# Mother_board_SSL2018.net
KiCad netlist of a schematic drawn in Altium Designer
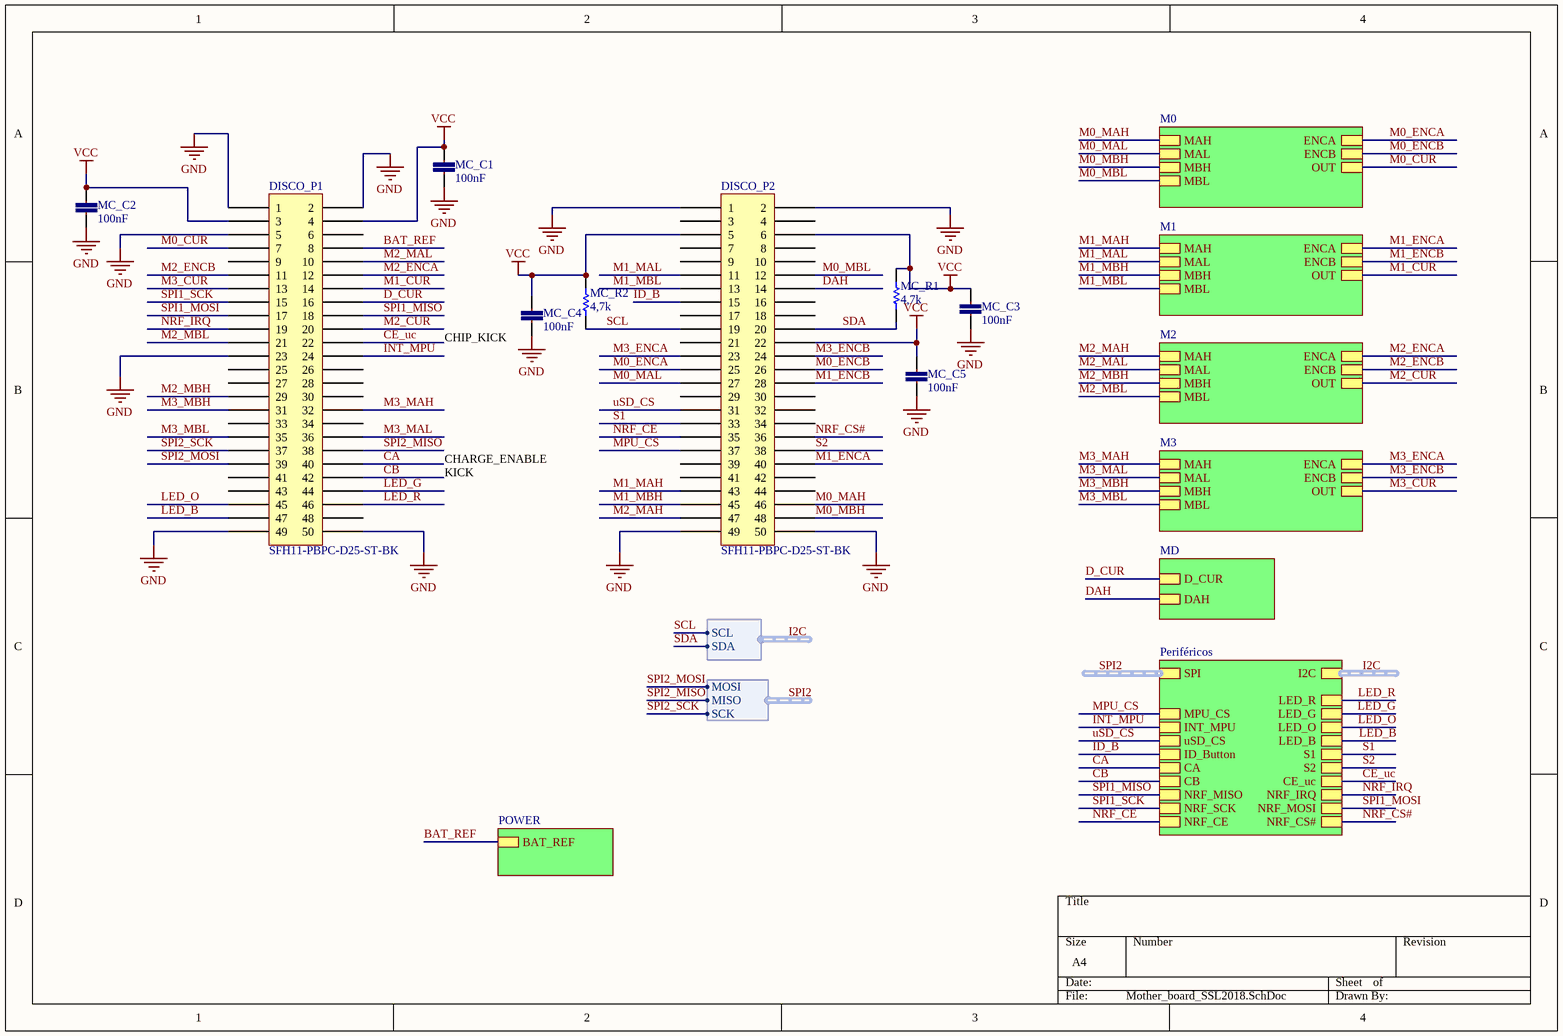
[diagram p0: Mother_board_SSL2018.SchDoc]

(export (version "E")
  (design (tool "Eeschema 10.0.6"))
  (components
    (comp (ref "DISCO_P1")
      (value "SFH11-PBPC-D25-ST-BK")
      (footprint "25x02_Conector_Female")
      (description "50 Position Header Connector 0.100\" (2.54mm) Through Hole Gold")
      (libsource (lib "Schlib1") (part "25x02_Conector_Female"))
    )
    (comp (ref "DISCO_P2")
      (value "SFH11-PBPC-D25-ST-BK")
      (footprint "25x02_Conector_Female")
      (description "50 Position Header Connector 0.100\" (2.54mm) Through Hole Gold")
      (libsource (lib "Schlib1") (part "25x02_Conector_Female"))
    )
    (comp (ref "MC_C1")
      (value "100nF")
      (footprint "0402-CAP")
      (description "CAP CER 0.1UF 10V 20% X5R 0402")
      (fields (field (name "PART NO") "VJ0402V104ZXQPBC"))
      (libsource (lib "") (part "CC0402-100nF-A.12_1"))
    )
    (comp (ref "MC_C2")
      (value "100nF")
      (footprint "0402-CAP")
      (description "CAP CER 0.1UF 10V 20% X5R 0402")
      (fields (field (name "PART NO") "VJ0402V104ZXQPBC"))
      (libsource (lib "IMBEL") (part "CC0402-100nF-A.12"))
    )
    (comp (ref "MC_C3")
      (value "100nF")
      (footprint "0402-CAP")
      (description "CAP CER 0.1UF 10V 20% X5R 0402")
      (fields (field (name "PART NO") "VJ0402V104ZXQPBC"))
      (libsource (lib "") (part "CC0402-100nF-A.12_1"))
    )
    (comp (ref "MC_C4")
      (value "100nF")
      (footprint "0402-CAP")
      (description "CAP CER 0.1UF 10V 20% X5R 0402")
      (fields (field (name "PART NO") "VJ0402V104ZXQPBC"))
      (libsource (lib "") (part "CC0402-100nF-A.12_1"))
    )
    (comp (ref "MC_C5")
      (value "100nF")
      (footprint "0402-CAP")
      (description "CAP CER 0.1UF 10V 20% X5R 0402")
      (fields (field (name "PART NO") "VJ0402V104ZXQPBC"))
      (libsource (lib "") (part "CC0402-100nF-A.12_1"))
    )
    (comp (ref "MC_R1")
      (value "4,7k")
      (footprint "0402")
      (description "Resistor")
      (fields (field (name "PUBLISHER") "Altium Limited"))
      (libsource (lib "Miscellaneous Devices") (part "Res1"))
    )
    (comp (ref "MC_R2")
      (value "4,7k")
      (footprint "0402")
      (description "Resistor")
      (fields (field (name "PUBLISHER") "Altium Limited"))
      (libsource (lib "Miscellaneous Devices") (part "Res1"))
    )
  )
  (nets
    (net (code "5") (name "/BAT_REF") (class "Default")
      (node (ref "DISCO_P1") (pin "8") (pinfunction "8_8") (pintype "passive"))
    )
    (net (code "6") (name "/CA") (class "Default")
      (node (ref "DISCO_P1") (pin "40") (pinfunction "40_40") (pintype "passive"))
    )
    (net (code "7") (name "/CB") (class "Default")
      (node (ref "DISCO_P1") (pin "42") (pinfunction "42_42") (pintype "passive"))
    )
    (net (code "8") (name "/CE_uc") (class "Default")
      (node (ref "DISCO_P1") (pin "22") (pinfunction "22_22") (pintype "passive"))
    )
    (net (code "9") (name "/DAH") (class "Default")
      (node (ref "DISCO_P2") (pin "14") (pinfunction "14_14") (pintype "passive"))
    )
    (net (code "10") (name "/D_CUR") (class "Default")
      (node (ref "DISCO_P1") (pin "16") (pinfunction "16_16") (pintype "passive"))
    )
    (net (code "12") (name "/ID_B") (class "Default")
      (node (ref "DISCO_P2") (pin "15") (pinfunction "15_15") (pintype "passive"))
    )
    (net (code "13") (name "/INT_MPU") (class "Default")
      (node (ref "DISCO_P1") (pin "24") (pinfunction "24_24") (pintype "passive"))
    )
    (net (code "14") (name "/LED_B") (class "Default")
      (node (ref "DISCO_P1") (pin "47") (pinfunction "47_47") (pintype "passive"))
    )
    (net (code "15") (name "/LED_G") (class "Default")
      (node (ref "DISCO_P1") (pin "44") (pinfunction "44_44") (pintype "passive"))
    )
    (net (code "16") (name "/LED_O") (class "Default")
      (node (ref "DISCO_P1") (pin "45") (pinfunction "45_45") (pintype "passive"))
    )
    (net (code "17") (name "/LED_R") (class "Default")
      (node (ref "DISCO_P1") (pin "46") (pinfunction "46_46") (pintype "passive"))
    )
    (net (code "18") (name "/M0_CUR") (class "Default")
      (node (ref "DISCO_P1") (pin "7") (pinfunction "7_7") (pintype "passive"))
    )
    (net (code "19") (name "/M0_ENCA") (class "Default")
      (node (ref "DISCO_P2") (pin "25") (pinfunction "25_25") (pintype "passive"))
    )
    (net (code "20") (name "/M0_ENCB") (class "Default")
      (node (ref "DISCO_P2") (pin "26") (pinfunction "26_26") (pintype "passive"))
    )
    (net (code "21") (name "/M0_MAH") (class "Default")
      (node (ref "DISCO_P2") (pin "46") (pinfunction "46_46") (pintype "passive"))
    )
    (net (code "22") (name "/M0_MAL") (class "Default")
      (node (ref "DISCO_P2") (pin "27") (pinfunction "27_27") (pintype "passive"))
    )
    (net (code "23") (name "/M0_MBH") (class "Default")
      (node (ref "DISCO_P2") (pin "48") (pinfunction "48_48") (pintype "passive"))
    )
    (net (code "24") (name "/M0_MBL") (class "Default")
      (node (ref "DISCO_P2") (pin "12") (pinfunction "12_12") (pintype "passive"))
    )
    (net (code "25") (name "/M1_CUR") (class "Default")
      (node (ref "DISCO_P1") (pin "14") (pinfunction "14_14") (pintype "passive"))
    )
    (net (code "26") (name "/M1_ENCA") (class "Default")
      (node (ref "DISCO_P2") (pin "40") (pinfunction "40_40") (pintype "passive"))
    )
    (net (code "27") (name "/M1_ENCB") (class "Default")
      (node (ref "DISCO_P2") (pin "28") (pinfunction "28_28") (pintype "passive"))
    )
    (net (code "28") (name "/M1_MAH") (class "Default")
      (node (ref "DISCO_P2") (pin "43") (pinfunction "43_43") (pintype "passive"))
    )
    (net (code "29") (name "/M1_MAL") (class "Default")
      (node (ref "DISCO_P2") (pin "11") (pinfunction "11_11") (pintype "passive"))
    )
    (net (code "30") (name "/M1_MBH") (class "Default")
      (node (ref "DISCO_P2") (pin "45") (pinfunction "45_45") (pintype "passive"))
    )
    (net (code "31") (name "/M1_MBL") (class "Default")
      (node (ref "DISCO_P2") (pin "13") (pinfunction "13_13") (pintype "passive"))
    )
    (net (code "32") (name "/M2_CUR") (class "Default")
      (node (ref "DISCO_P1") (pin "20") (pinfunction "20_20") (pintype "passive"))
    )
    (net (code "33") (name "/M2_ENCA") (class "Default")
      (node (ref "DISCO_P1") (pin "12") (pinfunction "12_12") (pintype "passive"))
    )
    (net (code "34") (name "/M2_ENCB") (class "Default")
      (node (ref "DISCO_P1") (pin "11") (pinfunction "11_11") (pintype "passive"))
    )
    (net (code "35") (name "/M2_MAH") (class "Default")
      (node (ref "DISCO_P2") (pin "47") (pinfunction "47_47") (pintype "passive"))
    )
    (net (code "36") (name "/M2_MAL") (class "Default")
      (node (ref "DISCO_P1") (pin "10") (pinfunction "10_10") (pintype "passive"))
    )
    (net (code "37") (name "/M2_MBH") (class "Default")
      (node (ref "DISCO_P1") (pin "29") (pinfunction "29_29") (pintype "passive"))
    )
    (net (code "38") (name "/M2_MBL") (class "Default")
      (node (ref "DISCO_P1") (pin "21") (pinfunction "21_21") (pintype "passive"))
    )
    (net (code "39") (name "/M3_CUR") (class "Default")
      (node (ref "DISCO_P1") (pin "13") (pinfunction "13_13") (pintype "passive"))
    )
    (net (code "40") (name "/M3_ENCA") (class "Default")
      (node (ref "DISCO_P2") (pin "23") (pinfunction "23_23") (pintype "passive"))
    )
    (net (code "41") (name "/M3_ENCB") (class "Default")
      (node (ref "DISCO_P2") (pin "24") (pinfunction "24_24") (pintype "passive"))
    )
    (net (code "42") (name "/M3_MAH") (class "Default")
      (node (ref "DISCO_P1") (pin "32") (pinfunction "32_32") (pintype "passive"))
    )
    (net (code "43") (name "/M3_MAL") (class "Default")
      (node (ref "DISCO_P1") (pin "36") (pinfunction "36_36") (pintype "passive"))
    )
    (net (code "44") (name "/M3_MBH") (class "Default")
      (node (ref "DISCO_P1") (pin "31") (pinfunction "31_31") (pintype "passive"))
    )
    (net (code "45") (name "/M3_MBL") (class "Default")
      (node (ref "DISCO_P1") (pin "35") (pinfunction "35_35") (pintype "passive"))
    )
    (net (code "46") (name "/MPU_CS") (class "Default")
      (node (ref "DISCO_P2") (pin "37") (pinfunction "37_37") (pintype "passive"))
    )
    (net (code "47") (name "/NRF_CE") (class "Default")
      (node (ref "DISCO_P2") (pin "35") (pinfunction "35_35") (pintype "passive"))
    )
    (net (code "48") (name "/NRF_CS#") (class "Default")
      (node (ref "DISCO_P2") (pin "36") (pinfunction "36_36") (pintype "passive"))
    )
    (net (code "49") (name "/NRF_IRQ") (class "Default")
      (node (ref "DISCO_P1") (pin "19") (pinfunction "19_19") (pintype "passive"))
    )
    (net (code "50") (name "/S1") (class "Default")
      (node (ref "DISCO_P2") (pin "33") (pinfunction "33_33") (pintype "passive"))
    )
    (net (code "51") (name "/S2") (class "Default")
      (node (ref "DISCO_P2") (pin "38") (pinfunction "38_38") (pintype "passive"))
    )
    (net (code "52") (name "/SCL") (class "Default")
      (node (ref "DISCO_P2") (pin "19") (pinfunction "19_19") (pintype "passive"))
      (node (ref "MC_R2") (pin "1") (pinfunction "1_1") (pintype "passive"))
    )
    (net (code "53") (name "/SDA") (class "Default")
      (node (ref "DISCO_P2") (pin "20") (pinfunction "20_20") (pintype "passive"))
      (node (ref "MC_R1") (pin "1") (pinfunction "1_1") (pintype "passive"))
    )
    (net (code "54") (name "/SPI1_MISO") (class "Default")
      (node (ref "DISCO_P1") (pin "18") (pinfunction "18_18") (pintype "passive"))
    )
    (net (code "55") (name "/SPI1_MOSI") (class "Default")
      (node (ref "DISCO_P1") (pin "17") (pinfunction "17_17") (pintype "passive"))
    )
    (net (code "56") (name "/SPI1_SCK") (class "Default")
      (node (ref "DISCO_P1") (pin "15") (pinfunction "15_15") (pintype "passive"))
    )
    (net (code "57") (name "/SPI2_MISO") (class "Default")
      (node (ref "DISCO_P1") (pin "38") (pinfunction "38_38") (pintype "passive"))
    )
    (net (code "58") (name "/SPI2_MOSI") (class "Default")
      (node (ref "DISCO_P1") (pin "39") (pinfunction "39_39") (pintype "passive"))
    )
    (net (code "59") (name "/SPI2_SCK") (class "Default")
      (node (ref "DISCO_P1") (pin "37") (pinfunction "37_37") (pintype "passive"))
    )
    (net (code "61") (name "/uSD_CS") (class "Default")
      (node (ref "DISCO_P2") (pin "31") (pinfunction "31_31") (pintype "passive"))
    )
    (net (code "64") (name "GND") (class "Default")
      (node (ref "DISCO_P1") (pin "1") (pinfunction "1_1") (pintype "passive"))
      (node (ref "DISCO_P1") (pin "2") (pinfunction "2_2") (pintype "passive"))
      (node (ref "DISCO_P1") (pin "23") (pinfunction "23_23") (pintype "passive"))
      (node (ref "DISCO_P1") (pin "49") (pinfunction "49_49") (pintype "passive"))
      (node (ref "DISCO_P1") (pin "5") (pinfunction "5_5") (pintype "passive"))
      (node (ref "DISCO_P1") (pin "50") (pinfunction "50_50") (pintype "passive"))
      (node (ref "DISCO_P2") (pin "1") (pinfunction "1_1") (pintype "passive"))
      (node (ref "DISCO_P2") (pin "2") (pinfunction "2_2") (pintype "passive"))
      (node (ref "DISCO_P2") (pin "49") (pinfunction "49_49") (pintype "passive"))
      (node (ref "DISCO_P2") (pin "50") (pinfunction "50_50") (pintype "passive"))
      (node (ref "MC_C1") (pin "1") (pinfunction "1_1") (pintype "passive"))
      (node (ref "MC_C2") (pin "2") (pinfunction "2_2") (pintype "passive"))
      (node (ref "MC_C3") (pin "1") (pinfunction "1_1") (pintype "passive"))
      (node (ref "MC_C4") (pin "1") (pinfunction "1_1") (pintype "passive"))
      (node (ref "MC_C5") (pin "1") (pinfunction "1_1") (pintype "passive"))
    )
    (net (code "65") (name "VCC") (class "Default")
      (node (ref "DISCO_P1") (pin "3") (pinfunction "3_3") (pintype "passive"))
      (node (ref "DISCO_P1") (pin "4") (pinfunction "4_4") (pintype "passive"))
      (node (ref "DISCO_P2") (pin "22") (pinfunction "22_22") (pintype "passive"))
      (node (ref "DISCO_P2") (pin "5") (pinfunction "5_5") (pintype "passive"))
      (node (ref "DISCO_P2") (pin "6") (pinfunction "6_6") (pintype "passive"))
      (node (ref "MC_C1") (pin "2") (pinfunction "2_2") (pintype "passive"))
      (node (ref "MC_C2") (pin "1") (pinfunction "1_1") (pintype "passive"))
      (node (ref "MC_C3") (pin "2") (pinfunction "2_2") (pintype "passive"))
      (node (ref "MC_C4") (pin "2") (pinfunction "2_2") (pintype "passive"))
      (node (ref "MC_C5") (pin "2") (pinfunction "2_2") (pintype "passive"))
      (node (ref "MC_R1") (pin "2") (pinfunction "2_2") (pintype "passive"))
      (node (ref "MC_R2") (pin "2") (pinfunction "2_2") (pintype "passive"))
    )
    (net (code "66") (name "unconnected-(DISCO_P1-Pad6)") (class "Default")
      (node (ref "DISCO_P1") (pin "6") (pinfunction "6_6") (pintype "passive"))
    )
    (net (code "67") (name "unconnected-(DISCO_P1-Pad9)") (class "Default")
      (node (ref "DISCO_P1") (pin "9") (pinfunction "9_9") (pintype "passive"))
    )
    (net (code "68") (name "unconnected-(DISCO_P1-Pad25)") (class "Default")
      (node (ref "DISCO_P1") (pin "25") (pinfunction "25_25") (pintype "passive"))
    )
    (net (code "69") (name "unconnected-(DISCO_P1-Pad26)") (class "Default")
      (node (ref "DISCO_P1") (pin "26") (pinfunction "26_26") (pintype "passive"))
    )
    (net (code "70") (name "unconnected-(DISCO_P1-Pad27)") (class "Default")
      (node (ref "DISCO_P1") (pin "27") (pinfunction "27_27") (pintype "passive"))
    )
    (net (code "71") (name "unconnected-(DISCO_P1-Pad28)") (class "Default")
      (node (ref "DISCO_P1") (pin "28") (pinfunction "28_28") (pintype "passive"))
    )
    (net (code "72") (name "unconnected-(DISCO_P1-Pad30)") (class "Default")
      (node (ref "DISCO_P1") (pin "30") (pinfunction "30_30") (pintype "passive"))
    )
    (net (code "73") (name "unconnected-(DISCO_P1-Pad33)") (class "Default")
      (node (ref "DISCO_P1") (pin "33") (pinfunction "33_33") (pintype "passive"))
    )
    (net (code "74") (name "unconnected-(DISCO_P1-Pad34)") (class "Default")
      (node (ref "DISCO_P1") (pin "34") (pinfunction "34_34") (pintype "passive"))
    )
    (net (code "75") (name "unconnected-(DISCO_P1-Pad41)") (class "Default")
      (node (ref "DISCO_P1") (pin "41") (pinfunction "41_41") (pintype "passive"))
    )
    (net (code "76") (name "unconnected-(DISCO_P1-Pad43)") (class "Default")
      (node (ref "DISCO_P1") (pin "43") (pinfunction "43_43") (pintype "passive"))
    )
    (net (code "77") (name "unconnected-(DISCO_P1-Pad48)") (class "Default")
      (node (ref "DISCO_P1") (pin "48") (pinfunction "48_48") (pintype "passive"))
    )
    (net (code "78") (name "unconnected-(DISCO_P2-Pad3)") (class "Default")
      (node (ref "DISCO_P2") (pin "3") (pinfunction "3_3") (pintype "passive"))
    )
    (net (code "79") (name "unconnected-(DISCO_P2-Pad4)") (class "Default")
      (node (ref "DISCO_P2") (pin "4") (pinfunction "4_4") (pintype "passive"))
    )
    (net (code "80") (name "unconnected-(DISCO_P2-Pad7)") (class "Default")
      (node (ref "DISCO_P2") (pin "7") (pinfunction "7_7") (pintype "passive"))
    )
    (net (code "81") (name "unconnected-(DISCO_P2-Pad8)") (class "Default")
      (node (ref "DISCO_P2") (pin "8") (pinfunction "8_8") (pintype "passive"))
    )
    (net (code "82") (name "unconnected-(DISCO_P2-Pad9)") (class "Default")
      (node (ref "DISCO_P2") (pin "9") (pinfunction "9_9") (pintype "passive"))
    )
    (net (code "83") (name "unconnected-(DISCO_P2-Pad10)") (class "Default")
      (node (ref "DISCO_P2") (pin "10") (pinfunction "10_10") (pintype "passive"))
    )
    (net (code "84") (name "unconnected-(DISCO_P2-Pad16)") (class "Default")
      (node (ref "DISCO_P2") (pin "16") (pinfunction "16_16") (pintype "passive"))
    )
    (net (code "85") (name "unconnected-(DISCO_P2-Pad17)") (class "Default")
      (node (ref "DISCO_P2") (pin "17") (pinfunction "17_17") (pintype "passive"))
    )
    (net (code "86") (name "unconnected-(DISCO_P2-Pad18)") (class "Default")
      (node (ref "DISCO_P2") (pin "18") (pinfunction "18_18") (pintype "passive"))
    )
    (net (code "87") (name "unconnected-(DISCO_P2-Pad21)") (class "Default")
      (node (ref "DISCO_P2") (pin "21") (pinfunction "21_21") (pintype "passive"))
    )
    (net (code "88") (name "unconnected-(DISCO_P2-Pad29)") (class "Default")
      (node (ref "DISCO_P2") (pin "29") (pinfunction "29_29") (pintype "passive"))
    )
    (net (code "89") (name "unconnected-(DISCO_P2-Pad30)") (class "Default")
      (node (ref "DISCO_P2") (pin "30") (pinfunction "30_30") (pintype "passive"))
    )
    (net (code "90") (name "unconnected-(DISCO_P2-Pad32)") (class "Default")
      (node (ref "DISCO_P2") (pin "32") (pinfunction "32_32") (pintype "passive"))
    )
    (net (code "91") (name "unconnected-(DISCO_P2-Pad34)") (class "Default")
      (node (ref "DISCO_P2") (pin "34") (pinfunction "34_34") (pintype "passive"))
    )
    (net (code "92") (name "unconnected-(DISCO_P2-Pad39)") (class "Default")
      (node (ref "DISCO_P2") (pin "39") (pinfunction "39_39") (pintype "passive"))
    )
    (net (code "93") (name "unconnected-(DISCO_P2-Pad41)") (class "Default")
      (node (ref "DISCO_P2") (pin "41") (pinfunction "41_41") (pintype "passive"))
    )
    (net (code "94") (name "unconnected-(DISCO_P2-Pad42)") (class "Default")
      (node (ref "DISCO_P2") (pin "42") (pinfunction "42_42") (pintype "passive"))
    )
    (net (code "95") (name "unconnected-(DISCO_P2-Pad44)") (class "Default")
      (node (ref "DISCO_P2") (pin "44") (pinfunction "44_44") (pintype "passive"))
    )
  )
)
